# BuckConverter.net
KiCad netlist of a schematic drawn in Altium Designer
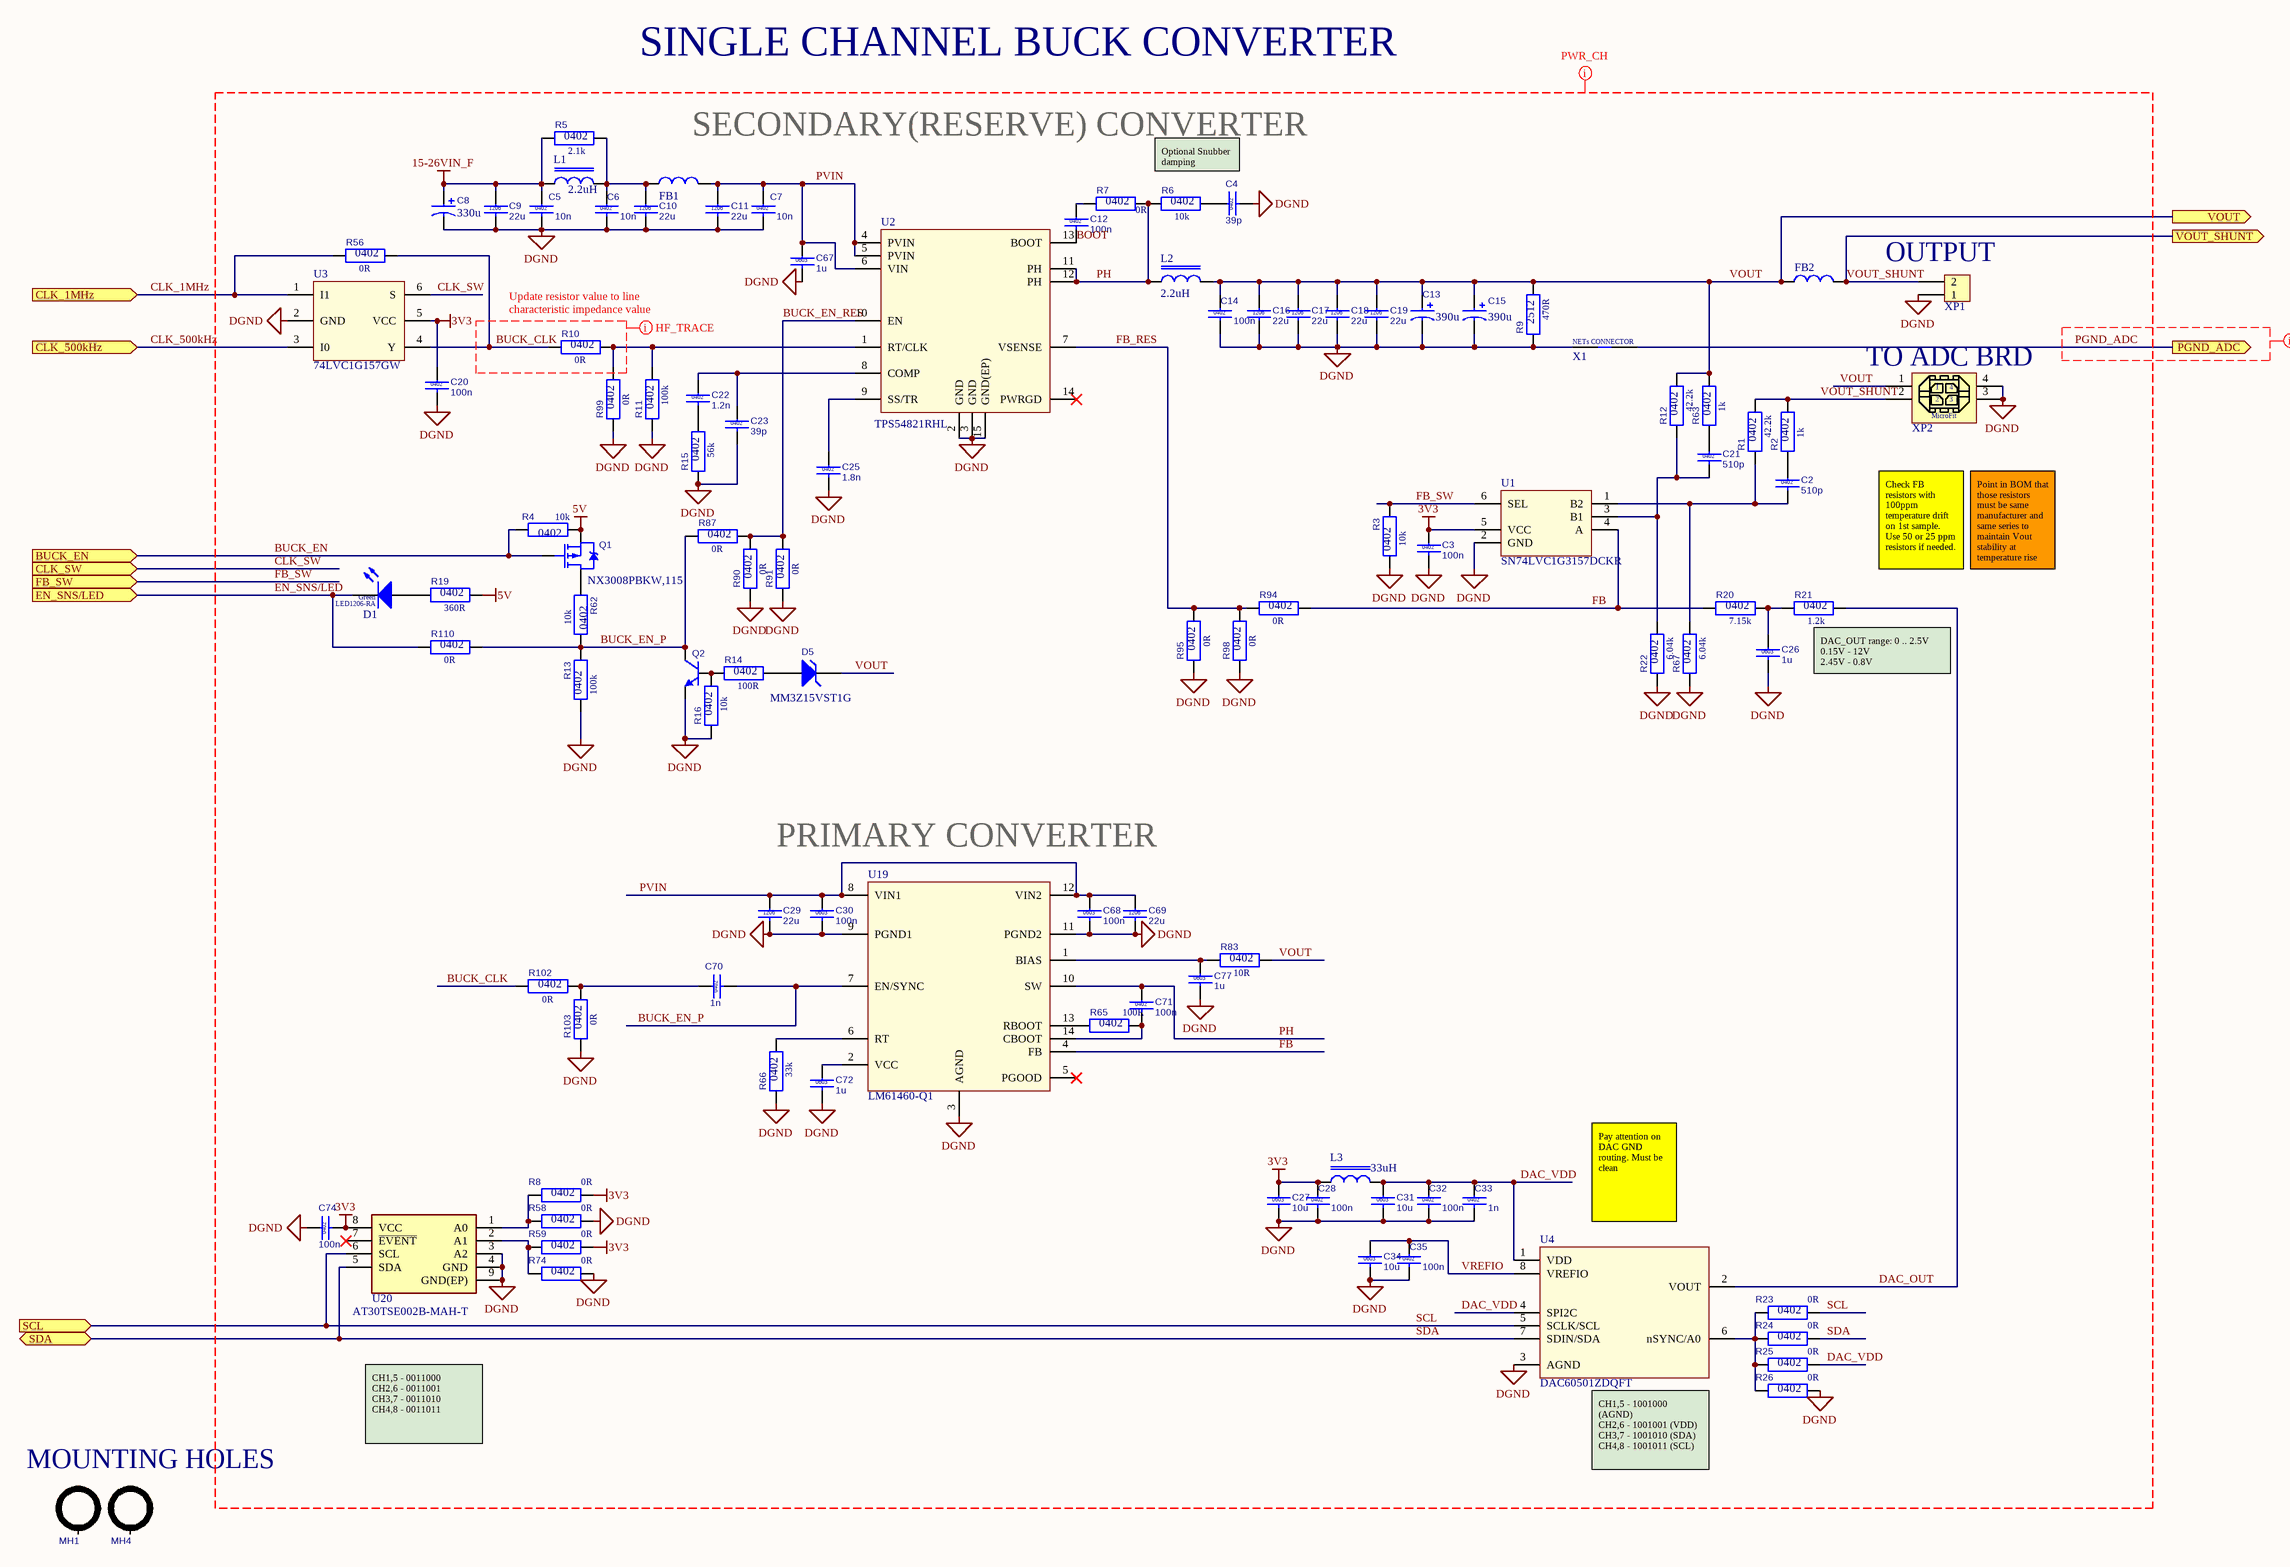
[diagram p0: BuckConverter.SchDoc]

(export (version "E")
  (design (tool "Eeschema 10.0.6"))
  (components
    (comp (ref "C2")
      (value "510p")
      (footprint "CC0402M")
      (description "Chip ceramic capacitor")
      (fields
        (field (name "CASE") "0402")
        (field (name "PARTNUMBER") "CC0402J-NP0-50V-510P-M")
        (field (name "MANUFACTURER") "Walsin")
      )
      (libsource (lib "AltiumLib") (part "Capacitor_nonpolar"))
    )
    (comp (ref "C3")
      (value "100n")
      (footprint "CC0402M")
      (description "Chip ceramic capacitor")
      (fields
        (field (name "CASE") "0402")
        (field (name "PARTNUMBER") "CC0402K-X7R-25V-100N-M")
        (field (name "MANUFACTURER") "Murata")
      )
      (libsource (lib "AltiumLib") (part "Capacitor_nonpolar"))
    )
    (comp (ref "C4")
      (value "39p")
      (footprint "CC0402M")
      (description "Chip ceramic capacitor")
      (fields
        (field (name "CASE") "0402")
        (field (name "PARTNUMBER") "CC0402J-NP0-50V-39P-M")
        (field (name "MANUFACTURER") "Yageo")
      )
      (libsource (lib "AltiumLib") (part "Capacitor_nonpolar"))
    )
    (comp (ref "C5")
      (value "10n")
      (footprint "CC0603M")
      (description "Chip ceramic capacitor")
      (fields
        (field (name "CASE") "0402")
        (field (name "PARTNUMBER") "CC0402K-X7R-50V-10N-M")
        (field (name "MANUFACTURER") "Yageo")
      )
      (libsource (lib "AltiumLib") (part "Capacitor_nonpolar"))
    )
    (comp (ref "C6")
      (value "10n")
      (footprint "CC0603M")
      (description "Chip ceramic capacitor")
      (fields
        (field (name "CASE") "0402")
        (field (name "PARTNUMBER") "CC0402K-X7R-50V-10N-M")
        (field (name "MANUFACTURER") "Yageo")
      )
      (libsource (lib "AltiumLib") (part "Capacitor_nonpolar"))
    )
    (comp (ref "C7")
      (value "10n")
      (footprint "CC0603M")
      (description "Chip ceramic capacitor")
      (fields
        (field (name "CASE") "0402")
        (field (name "PARTNUMBER") "CC0402K-X7R-50V-10N-M")
        (field (name "MANUFACTURER") "Yageo")
      )
      (libsource (lib "AltiumLib") (part "Capacitor_nonpolar"))
    )
    (comp (ref "C8")
      (value "330u")
      (footprint "CA-D10H10.5-SMD")
      (description "Aluminium Electrlytic capacitor")
      (fields (field (name "PARTNUMBER") "CE-L10D10-330U-35V-SMD") (field (name "MANUFACTURER") "Kemet"))
      (libsource (lib "AltiumLib") (part "Capacitor_polar"))
    )
    (comp (ref "C9")
      (value "22u")
      (footprint "CC1206M")
      (description "Chip ceramic capacitor")
      (fields
        (field (name "CASE") "1206")
        (field (name "PARTNUMBER") "CC1206K-X5R-35V-22U-M")
        (field (name "MANUFACTURER") "TDK")
      )
      (libsource (lib "AltiumLib") (part "Capacitor_nonpolar"))
    )
    (comp (ref "C10")
      (value "22u")
      (footprint "CC1206M")
      (description "Chip ceramic capacitor")
      (fields
        (field (name "CASE") "1206")
        (field (name "PARTNUMBER") "CC1206K-X5R-35V-22U-M")
        (field (name "MANUFACTURER") "TDK")
      )
      (libsource (lib "AltiumLib") (part "Capacitor_nonpolar"))
    )
    (comp (ref "C11")
      (value "22u")
      (footprint "CC1206M")
      (description "Chip ceramic capacitor")
      (fields
        (field (name "CASE") "1206")
        (field (name "PARTNUMBER") "CC1206K-X5R-35V-22U-M")
        (field (name "MANUFACTURER") "TDK")
      )
      (libsource (lib "AltiumLib") (part "Capacitor_nonpolar"))
    )
    (comp (ref "C12")
      (value "100n")
      (footprint "CC0402M")
      (description "Chip ceramic capacitor")
      (fields
        (field (name "CASE") "0402")
        (field (name "PARTNUMBER") "CC0402K-X7R-25V-100N-M")
        (field (name "MANUFACTURER") "Murata")
      )
      (libsource (lib "AltiumLib") (part "Capacitor_nonpolar"))
    )
    (comp (ref "C13")
      (value "390u")
      (footprint "CA-D8H12-SMD")
      (description "Aluminium polymer capacitor")
      (fields (field (name "PARTNUMBER") "20SVPF390M") (field (name "MANUFACTURER") "Panasonic"))
      (libsource (lib "AltiumLib") (part "Capacitor_polar"))
    )
    (comp (ref "C14")
      (value "100n")
      (footprint "CC0402M")
      (description "Chip ceramic capacitor")
      (fields
        (field (name "CASE") "0402")
        (field (name "PARTNUMBER") "CC0402K-X7R-25V-100N-M")
        (field (name "MANUFACTURER") "Murata")
      )
      (libsource (lib "AltiumLib") (part "Capacitor_nonpolar"))
    )
    (comp (ref "C15")
      (value "390u")
      (footprint "CA-D8H12-SMD")
      (description "Aluminium polymer capacitor")
      (fields (field (name "PARTNUMBER") "20SVPF390M") (field (name "MANUFACTURER") "Panasonic"))
      (libsource (lib "AltiumLib") (part "Capacitor_polar"))
    )
    (comp (ref "C16")
      (value "22u")
      (footprint "CC1206M")
      (description "Chip ceramic capacitor")
      (fields
        (field (name "CASE") "1206")
        (field (name "PARTNUMBER") "CC1206K-X5R-25V-22U-M")
        (field (name "MANUFACTURER") "Samsung")
      )
      (libsource (lib "AltiumLib") (part "Capacitor_nonpolar"))
    )
    (comp (ref "C17")
      (value "22u")
      (footprint "CC1206M")
      (description "Chip ceramic capacitor")
      (fields
        (field (name "CASE") "1206")
        (field (name "PARTNUMBER") "CC1206K-X5R-25V-22U-M")
        (field (name "MANUFACTURER") "Samsung")
      )
      (libsource (lib "AltiumLib") (part "Capacitor_nonpolar"))
    )
    (comp (ref "C18")
      (value "22u")
      (footprint "CC1206M")
      (description "Chip ceramic capacitor")
      (fields
        (field (name "CASE") "1206")
        (field (name "PARTNUMBER") "CC1206K-X5R-25V-22U-M")
        (field (name "MANUFACTURER") "Samsung")
      )
      (libsource (lib "AltiumLib") (part "Capacitor_nonpolar"))
    )
    (comp (ref "C19")
      (value "22u")
      (footprint "CC1206M")
      (description "Chip ceramic capacitor")
      (fields
        (field (name "CASE") "1206")
        (field (name "PARTNUMBER") "CC1206K-X5R-25V-22U-M")
        (field (name "MANUFACTURER") "Samsung")
      )
      (libsource (lib "AltiumLib") (part "Capacitor_nonpolar"))
    )
    (comp (ref "C20")
      (value "100n")
      (footprint "CC0402M")
      (description "Chip ceramic capacitor")
      (fields
        (field (name "CASE") "0402")
        (field (name "PARTNUMBER") "CC0402K-X7R-25V-100N-M")
        (field (name "MANUFACTURER") "Murata")
      )
      (libsource (lib "AltiumLib") (part "Capacitor_nonpolar"))
    )
    (comp (ref "C21")
      (value "510p")
      (footprint "CC0402M")
      (description "Chip ceramic capacitor")
      (fields
        (field (name "CASE") "0402")
        (field (name "PARTNUMBER") "CC0402J-NP0-50V-510P-M")
        (field (name "MANUFACTURER") "Walsin")
      )
      (libsource (lib "AltiumLib") (part "Capacitor_nonpolar"))
    )
    (comp (ref "C22")
      (value "1.2n")
      (footprint "CC0402M")
      (description "Chip ceramic capacitor")
      (fields
        (field (name "CASE") "0402")
        (field (name "PARTNUMBER") "CC0402K-X7R-50V-1N2-M")
        (field (name "MANUFACTURER") "Yageo")
      )
      (libsource (lib "AltiumLib") (part "Capacitor_nonpolar"))
    )
    (comp (ref "C23")
      (value "39p")
      (footprint "CC0402M")
      (description "Chip ceramic capacitor")
      (fields
        (field (name "CASE") "0402")
        (field (name "PARTNUMBER") "CC0402J-NP0-50V-39P-M")
        (field (name "MANUFACTURER") "Yageo")
      )
      (libsource (lib "AltiumLib") (part "Capacitor_nonpolar"))
    )
    (comp (ref "C25")
      (value "1.8n")
      (footprint "CC0402M")
      (description "Chip ceramic capacitor")
      (fields
        (field (name "CASE") "0402")
        (field (name "PARTNUMBER") "CC0402K-X7R-50V-1N8-M")
        (field (name "MANUFACTURER") "Yageo")
      )
      (libsource (lib "AltiumLib") (part "Capacitor_nonpolar"))
    )
    (comp (ref "C26")
      (value "1u")
      (footprint "CC0603M")
      (description "Chip ceramic capacitor")
      (fields
        (field (name "CASE") "0603")
        (field (name "PARTNUMBER") "CC0603K-X7R-10V-1U-M")
        (field (name "MANUFACTURER") "Samsung")
      )
      (libsource (lib "AltiumLib") (part "Capacitor_nonpolar"))
    )
    (comp (ref "C27")
      (value "10u")
      (footprint "CC0603M")
      (description "Chip ceramic capacitor")
      (fields
        (field (name "CASE") "0603")
        (field (name "PARTNUMBER") "CC0603K-X5R-10V-10U-M")
        (field (name "MANUFACTURER") "Murata")
      )
      (libsource (lib "AltiumLib") (part "Capacitor_nonpolar"))
    )
    (comp (ref "C28")
      (value "100n")
      (footprint "CC0402M")
      (description "Chip ceramic capacitor")
      (fields
        (field (name "CASE") "0402")
        (field (name "PARTNUMBER") "CC0402K-X7R-25V-100N-M")
        (field (name "MANUFACTURER") "Murata")
      )
      (libsource (lib "AltiumLib") (part "Capacitor_nonpolar"))
    )
    (comp (ref "C29")
      (value "22u")
      (footprint "CC1206M")
      (description "Chip ceramic capacitor")
      (fields
        (field (name "CASE") "1206")
        (field (name "PARTNUMBER") "CC1206K-X5R-35V-22U-M")
        (field (name "MANUFACTURER") "TDK")
      )
      (libsource (lib "AltiumLib") (part "Capacitor_nonpolar"))
    )
    (comp (ref "C30")
      (value "100n")
      (footprint "CC0603M")
      (description "Chip ceramic capacitor")
      (fields
        (field (name "CASE") "0603")
        (field (name "PARTNUMBER") "CC0603K-X7R-50V-100N-M")
        (field (name "MANUFACTURER") "Yageo")
      )
      (libsource (lib "AltiumLib") (part "Capacitor_nonpolar"))
    )
    (comp (ref "C31")
      (value "10u")
      (footprint "CC0603M")
      (description "Chip ceramic capacitor")
      (fields
        (field (name "CASE") "0603")
        (field (name "PARTNUMBER") "CC0603K-X5R-10V-10U-M")
        (field (name "MANUFACTURER") "Murata")
      )
      (libsource (lib "AltiumLib") (part "Capacitor_nonpolar"))
    )
    (comp (ref "C32")
      (value "100n")
      (footprint "CC0402M")
      (description "Chip ceramic capacitor")
      (fields
        (field (name "CASE") "0402")
        (field (name "PARTNUMBER") "CC0402K-X7R-25V-100N-M")
        (field (name "MANUFACTURER") "Murata")
      )
      (libsource (lib "AltiumLib") (part "Capacitor_nonpolar"))
    )
    (comp (ref "C33")
      (value "1n")
      (footprint "CC0402M")
      (description "Chip ceramic capacitor")
      (fields
        (field (name "CASE") "0402")
        (field (name "PARTNUMBER") "CC0402K-X7R-50V-1N-M")
        (field (name "MANUFACTURER") "Yageo")
      )
      (libsource (lib "AltiumLib") (part "Capacitor_nonpolar"))
    )
    (comp (ref "C34")
      (value "10u")
      (footprint "CC0603M")
      (description "Chip ceramic capacitor")
      (fields
        (field (name "CASE") "0603")
        (field (name "PARTNUMBER") "CC0603K-X5R-10V-10U-M")
        (field (name "MANUFACTURER") "Murata")
      )
      (libsource (lib "AltiumLib") (part "Capacitor_nonpolar"))
    )
    (comp (ref "C35")
      (value "100n")
      (footprint "CC0402M")
      (description "Chip ceramic capacitor")
      (fields
        (field (name "CASE") "0402")
        (field (name "PARTNUMBER") "CC0402K-X7R-25V-100N-M")
        (field (name "MANUFACTURER") "Murata")
      )
      (libsource (lib "AltiumLib") (part "Capacitor_nonpolar"))
    )
    (comp (ref "C67")
      (value "1u")
      (footprint "CC0603M")
      (description "Chip ceramic capacitor")
      (fields
        (field (name "CASE") "0603")
        (field (name "PARTNUMBER") "CC0603K-X5R-50V-1U-M")
        (field (name "MANUFACTURER") "Samsung")
      )
      (libsource (lib "AltiumLib") (part "Capacitor_nonpolar"))
    )
    (comp (ref "C68")
      (value "100n")
      (footprint "CC0603M")
      (description "Chip ceramic capacitor")
      (fields
        (field (name "CASE") "0603")
        (field (name "PARTNUMBER") "CC0603K-X7R-50V-100N-M")
        (field (name "MANUFACTURER") "Yageo")
      )
      (libsource (lib "AltiumLib") (part "Capacitor_nonpolar"))
    )
    (comp (ref "C69")
      (value "22u")
      (footprint "CC1206M")
      (description "Chip ceramic capacitor")
      (fields
        (field (name "CASE") "1206")
        (field (name "PARTNUMBER") "CC1206K-X5R-35V-22U-M")
        (field (name "MANUFACTURER") "TDK")
      )
      (libsource (lib "AltiumLib") (part "Capacitor_nonpolar"))
    )
    (comp (ref "C70")
      (value "1n")
      (footprint "CC0402M")
      (description "Chip ceramic capacitor")
      (fields
        (field (name "CASE") "0402")
        (field (name "PARTNUMBER") "CC0402K-X7R-50V-1N-M")
        (field (name "MANUFACTURER") "Yageo")
      )
      (libsource (lib "AltiumLib") (part "Capacitor_nonpolar"))
    )
    (comp (ref "C71")
      (value "100n")
      (footprint "CC0402M")
      (description "Chip ceramic capacitor")
      (fields
        (field (name "CASE") "0402")
        (field (name "PARTNUMBER") "CC0402K-X7R-25V-100N-M")
        (field (name "MANUFACTURER") "Murata")
      )
      (libsource (lib "AltiumLib") (part "Capacitor_nonpolar"))
    )
    (comp (ref "C72")
      (value "1u")
      (footprint "CC0603M")
      (description "Chip ceramic capacitor")
      (fields
        (field (name "CASE") "0603")
        (field (name "PARTNUMBER") "CC0603K-X5R-50V-1U-M")
        (field (name "MANUFACTURER") "Samsung")
      )
      (libsource (lib "AltiumLib") (part "Capacitor_nonpolar"))
    )
    (comp (ref "C74")
      (value "100n")
      (footprint "CC0402M")
      (description "Chip ceramic capacitor")
      (fields
        (field (name "CASE") "0402")
        (field (name "PARTNUMBER") "CC0402K-X7R-25V-100N-M")
        (field (name "MANUFACTURER") "Murata")
      )
      (libsource (lib "AltiumLib") (part "Capacitor_nonpolar"))
    )
    (comp (ref "C77")
      (value "1u")
      (footprint "CC0603M")
      (description "Chip ceramic capacitor")
      (fields
        (field (name "CASE") "0603")
        (field (name "PARTNUMBER") "CC0603K-X5R-50V-1U-M")
        (field (name "MANUFACTURER") "Samsung")
      )
      (libsource (lib "AltiumLib") (part "Capacitor_nonpolar"))
    )
    (comp (ref "D1")
      (value "155124GS73200A")
      (footprint "LED1206-RA")
      (description "LED GREEN CLEAR 1206 SMD RA")
      (fields
        (field (name "CASE") "LED1206-RA")
        (field (name "COLOR") "Green")
        (field (name "MANUFACTURER") "Würth Elektronik")
      )
      (libsource (lib "AltiumLib") (part "LED"))
    )
    (comp (ref "D5")
      (value "MM3Z15VST1G")
      (footprint "SOD323")
      (description "Zener Diode 14.66V 300mW ±2% Surface Mount SOD-323")
      (fields (field (name "MANUFACTURER") "ON Semiconductor"))
      (libsource (lib "AltiumLib") (part "ZENNER_DIODE"))
    )
    (comp (ref "FB1")
      (value "BLM21SP601SH1D")
      (footprint "FB0805M")
      (description "600 Ohms @ 100MHz 1 Power Line Ferrite Bead 0805 (2012 Metric) 2.3A")
      (fields (field (name "MANUFACTURER") "Murata"))
      (libsource (lib "AltiumLib") (part "FerriteBead"))
    )
    (comp (ref "FB2")
      (value "BLM18KG260TN1D")
      (footprint "FB0603M")
      (description "26 Ohms @ 100MHz 1 Power Line Ferrite Bead 0603 (1608 Metric) 6A 7mOhm")
      (fields (field (name "MANUFACTURER") "Murata"))
      (libsource (lib "AltiumLib") (part "FerriteBead"))
    )
    (comp (ref "L1")
      (value "2.2uH")
      (footprint "MGV252010S")
      (description "2.2µH Shielded Molded Inductor 2.4A 110mOhm Max 1008 (2520 Metric)")
      (fields
        (field (name "PARTNUMBER") "MGV252010S2R2M-10")
        (field (name "MANUFACTURER") "Laird-Signal Integrity Products")
      )
      (libsource (lib "AltiumLib") (part "Inductor"))
    )
    (comp (ref "L2")
      (value "2.2uH")
      (footprint "104CDMCCDS")
      (description "FIXED IND 2.2UH 15A 7 MOHM")
      (fields (field (name "PARTNUMBER") "104CDMCCDS-2R2MC") (field (name "MANUFACTURER") "Sumida"))
      (libsource (lib "AltiumLib") (part "Inductor"))
    )
    (comp (ref "L3")
      (value "33uH")
      (footprint "IC0805-M")
      (description "FIXED IND 33UH 5MA 1.25 OHM SMD")
      (fields (field (name "PARTNUMBER") "CV201210-330K") (field (name "MANUFACTURER") "Bourns"))
      (libsource (lib "AltiumLib") (part "Inductor"))
    )
    (comp (ref "MH1")
      (value "MH-3.5-PLATED")
      (footprint "MH_3.5_PLATED")
      (description "Mounting Hole")
      (fields (field (name "MANUFACTURER") "NULL"))
      (libsource (lib "AltiumLib") (part "MH_MISC"))
    )
    (comp (ref "MH4")
      (value "MH-3.5-PLATED")
      (footprint "MH_3.5_PLATED")
      (description "Mounting Hole")
      (fields (field (name "MANUFACTURER") "NULL"))
      (libsource (lib "AltiumLib") (part "MH_MISC"))
    )
    (comp (ref "Q1")
      (value "NX3008PBKW,115")
      (footprint "SOT323")
      (description "P-Channel 30V 200mA (Ta) 260mW (Ta), 830mW (Tc) Surface Mount SC-70")
      (fields (field (name "MANUFACTURER") "Nexperia"))
      (libsource (lib "AltiumLib") (part "MOSFET_P-CH"))
    )
    (comp (ref "Q2")
      (value "NPN_transistor_SOT23-3")
      (footprint "SOT323")
      (description "TRANS NPN 40V 0.2A SOT323")
      (fields (field (name "PARTNUMBER") "MMBT3904WT1G") (field (name "MANUFACTURER") "ON Semiconductor"))
      (libsource (lib "AltiumLib") (part "NPN_SOT23-3"))
    )
    (comp (ref "R1")
      (value "42.2k")
      (footprint "RC0402M")
      (description "Chip resistor")
      (fields
        (field (name "CASE") "0402")
        (field (name "PARTNUMBER") "RC0402F-42K2-M")
        (field (name "POWER") "0.063W")
      )
      (libsource (lib "AltiumLib") (part "Resistor"))
    )
    (comp (ref "R2")
      (value "1k")
      (footprint "RC0402M")
      (description "Chip resistor")
      (fields
        (field (name "CASE") "0402")
        (field (name "PARTNUMBER") "RC0402F-1K-M")
        (field (name "MANUFACTURER") "Yageo")
      )
      (libsource (lib "AltiumLib") (part "Resistor"))
    )
    (comp (ref "R3")
      (value "10k")
      (footprint "RC0402M")
      (description "Chip resistor")
      (fields
        (field (name "CASE") "0402")
        (field (name "PARTNUMBER") "RC0402F-10K-M")
        (field (name "MANUFACTURER") "Yageo")
      )
      (libsource (lib "AltiumLib") (part "Resistor"))
    )
    (comp (ref "R4")
      (value "10k")
      (footprint "RC0402M")
      (description "Chip resistor")
      (fields
        (field (name "CASE") "0402")
        (field (name "PARTNUMBER") "RC0402F-10K-M")
        (field (name "MANUFACTURER") "Yageo")
      )
      (libsource (lib "AltiumLib") (part "Resistor"))
    )
    (comp (ref "R5")
      (value "2.1k")
      (footprint "RC0402M")
      (description "Chip resistor")
      (fields
        (field (name "CASE") "0402")
        (field (name "PARTNUMBER") "RC0402F-2K1-M")
        (field (name "POWER") "0.063W")
      )
      (libsource (lib "AltiumLib") (part "Resistor"))
    )
    (comp (ref "R6")
      (value "10k")
      (footprint "RC0402M")
      (description "Chip resistor")
      (fields
        (field (name "CASE") "0402")
        (field (name "PARTNUMBER") "RC0402F-10K-M")
        (field (name "POWER") "0.063W")
      )
      (libsource (lib "AltiumLib") (part "Resistor"))
    )
    (comp (ref "R7")
      (value "0R")
      (footprint "RC0402M")
      (description "Chip resistor")
      (fields
        (field (name "CASE") "0402")
        (field (name "PARTNUMBER") "RC0402F-0R-M")
        (field (name "POWER") "0.063W")
      )
      (libsource (lib "AltiumLib") (part "Resistor"))
    )
    (comp (ref "R8")
      (value "0R")
      (footprint "RC0402M")
      (description "Chip resistor")
      (fields
        (field (name "CASE") "0402")
        (field (name "PARTNUMBER") "RC0402F-0R-M")
        (field (name "POWER") "0.063W")
      )
      (libsource (lib "AltiumLib") (part "Resistor"))
    )
    (comp (ref "R9")
      (value "470R")
      (footprint "RC2512M")
      (description "Chip resistor")
      (fields
        (field (name "CASE") "2512")
        (field (name "PARTNUMBER") "RC2512J-479R-M")
        (field (name "MANUFACTURER") "Stackpole")
      )
      (libsource (lib "AltiumLib") (part "Resistor"))
    )
    (comp (ref "R10")
      (value "0R")
      (footprint "RC0402M")
      (description "Chip resistor")
      (fields
        (field (name "CASE") "0402")
        (field (name "PARTNUMBER") "RC0402F-0R-M")
        (field (name "POWER") "0.063W")
      )
      (libsource (lib "AltiumLib") (part "Resistor"))
    )
    (comp (ref "R11")
      (value "100k")
      (footprint "RC0402M")
      (description "Chip resistor")
      (fields
        (field (name "CASE") "0402")
        (field (name "PARTNUMBER") "RC0402F-100K-M")
        (field (name "POWER") "0.063W")
      )
      (libsource (lib "AltiumLib") (part "Resistor"))
    )
    (comp (ref "R12")
      (value "42.2k")
      (footprint "RC0402M")
      (description "Chip resistor")
      (fields
        (field (name "CASE") "0402")
        (field (name "PARTNUMBER") "RC0402F-42K2-M")
        (field (name "POWER") "0.063W")
      )
      (libsource (lib "AltiumLib") (part "Resistor"))
    )
    (comp (ref "R13")
      (value "100k")
      (footprint "RC0402M")
      (description "Chip resistor")
      (fields
        (field (name "CASE") "0402")
        (field (name "PARTNUMBER") "RC0402F-100K-M")
        (field (name "MANUFACTURER") "Yageo")
      )
      (libsource (lib "AltiumLib") (part "Resistor"))
    )
    (comp (ref "R14")
      (value "100R")
      (footprint "RC0402M")
      (description "Chip resistor")
      (fields
        (field (name "CASE") "0402")
        (field (name "PARTNUMBER") "RC0402F-100R-M")
        (field (name "MANUFACTURER") "Yageo")
      )
      (libsource (lib "AltiumLib") (part "Resistor"))
    )
    (comp (ref "R15")
      (value "56k")
      (footprint "RC0402M")
      (description "Chip resistor")
      (fields
        (field (name "CASE") "0402")
        (field (name "PARTNUMBER") "RC0402F-56K-M")
        (field (name "POWER") "0.063W")
      )
      (libsource (lib "AltiumLib") (part "Resistor"))
    )
    (comp (ref "R16")
      (value "10k")
      (footprint "RC0402M")
      (description "Chip resistor")
      (fields
        (field (name "CASE") "0402")
        (field (name "PARTNUMBER") "RC0402F-10K-M")
        (field (name "MANUFACTURER") "Yageo")
      )
      (libsource (lib "AltiumLib") (part "Resistor"))
    )
    (comp (ref "R19")
      (value "360R")
      (footprint "RC0402M")
      (description "Chip resistor")
      (fields
        (field (name "CASE") "0402")
        (field (name "PARTNUMBER") "RC0402F-360R-M")
        (field (name "MANUFACTURER") "Yageo")
      )
      (libsource (lib "AltiumLib") (part "Resistor"))
    )
    (comp (ref "R20")
      (value "7.15k")
      (footprint "RC0402M")
      (description "Chip resistor")
      (fields
        (field (name "CASE") "0402")
        (field (name "PARTNUMBER") "RC0402F-7K15-M")
        (field (name "MANUFACTURER") "Yageo")
      )
      (libsource (lib "AltiumLib") (part "Resistor"))
    )
    (comp (ref "R21")
      (value "1.2k")
      (footprint "RC0402M")
      (description "Chip resistor")
      (fields
        (field (name "CASE") "0402")
        (field (name "PARTNUMBER") "RC0402F-1K2-M")
        (field (name "MANUFACTURER") "Yageo")
      )
      (libsource (lib "AltiumLib") (part "Resistor"))
    )
    (comp (ref "R22")
      (value "6.04k")
      (footprint "RC0402M")
      (description "Chip resistor")
      (fields
        (field (name "CASE") "0402")
        (field (name "PARTNUMBER") "RC0402F-6K04-M")
        (field (name "MANUFACTURER") "Yageo")
      )
      (libsource (lib "AltiumLib") (part "Resistor"))
    )
    (comp (ref "R23")
      (value "0R")
      (footprint "RC0402M")
      (description "Chip resistor")
      (fields
        (field (name "CASE") "0402")
        (field (name "PARTNUMBER") "RC0402F-0R-M")
        (field (name "POWER") "0.063W")
      )
      (libsource (lib "AltiumLib") (part "Resistor"))
    )
    (comp (ref "R24")
      (value "0R")
      (footprint "RC0402M")
      (description "Chip resistor")
      (fields
        (field (name "CASE") "0402")
        (field (name "PARTNUMBER") "RC0402F-0R-M")
        (field (name "POWER") "0.063W")
      )
      (libsource (lib "AltiumLib") (part "Resistor"))
    )
    (comp (ref "R25")
      (value "0R")
      (footprint "RC0402M")
      (description "Chip resistor")
      (fields
        (field (name "CASE") "0402")
        (field (name "PARTNUMBER") "RC0402F-0R-M")
        (field (name "POWER") "0.063W")
      )
      (libsource (lib "AltiumLib") (part "Resistor"))
    )
    (comp (ref "R26")
      (value "0R")
      (footprint "RC0402M")
      (description "Chip resistor")
      (fields
        (field (name "CASE") "0402")
        (field (name "PARTNUMBER") "RC0402F-0R-M")
        (field (name "POWER") "0.063W")
      )
      (libsource (lib "AltiumLib") (part "Resistor"))
    )
    (comp (ref "R56")
      (value "0R")
      (footprint "RC0402M")
      (description "Chip resistor")
      (fields
        (field (name "CASE") "0402")
        (field (name "PARTNUMBER") "RC0402F-0R-M")
        (field (name "POWER") "0.063W")
      )
      (libsource (lib "AltiumLib") (part "Resistor"))
    )
    (comp (ref "R58")
      (value "0R")
      (footprint "RC0402M")
      (description "Chip resistor")
      (fields
        (field (name "CASE") "0402")
        (field (name "PARTNUMBER") "RC0402F-0R-M")
        (field (name "POWER") "0.063W")
      )
      (libsource (lib "AltiumLib") (part "Resistor"))
    )
    (comp (ref "R59")
      (value "0R")
      (footprint "RC0402M")
      (description "Chip resistor")
      (fields
        (field (name "CASE") "0402")
        (field (name "PARTNUMBER") "RC0402F-0R-M")
        (field (name "POWER") "0.063W")
      )
      (libsource (lib "AltiumLib") (part "Resistor"))
    )
    (comp (ref "R62")
      (value "10k")
      (footprint "RC0402M")
      (description "Chip resistor")
      (fields
        (field (name "CASE") "0402")
        (field (name "PARTNUMBER") "RC0402F-10K-M")
        (field (name "MANUFACTURER") "Yageo")
      )
      (libsource (lib "AltiumLib") (part "Resistor"))
    )
    (comp (ref "R63")
      (value "1k")
      (footprint "RC0402M")
      (description "Chip resistor")
      (fields
        (field (name "CASE") "0402")
        (field (name "PARTNUMBER") "RC0402F-1K-M")
        (field (name "MANUFACTURER") "Yageo")
      )
      (libsource (lib "AltiumLib") (part "Resistor"))
    )
    (comp (ref "R65")
      (value "100R")
      (footprint "RC0402M")
      (description "Chip resistor")
      (fields
        (field (name "CASE") "0402")
        (field (name "PARTNUMBER") "RC0402F-100R-M")
        (field (name "MANUFACTURER") "Yageo")
      )
      (libsource (lib "AltiumLib") (part "Resistor"))
    )
    (comp (ref "R66")
      (value "33k")
      (footprint "RC0402M")
      (description "Chip resistor")
      (fields
        (field (name "CASE") "0402")
        (field (name "PARTNUMBER") "RC0402F-33K-M")
        (field (name "MANUFACTURER") "Yageo")
      )
      (libsource (lib "AltiumLib") (part "Resistor"))
    )
    (comp (ref "R67")
      (value "6.04k")
      (footprint "RC0402M")
      (description "Chip resistor")
      (fields
        (field (name "CASE") "0402")
        (field (name "PARTNUMBER") "RC0402F-6K04-M")
        (field (name "MANUFACTURER") "Yageo")
      )
      (libsource (lib "AltiumLib") (part "Resistor"))
    )
    (comp (ref "R74")
      (value "0R")
      (footprint "RC0402M")
      (description "Chip resistor")
      (fields
        (field (name "CASE") "0402")
        (field (name "PARTNUMBER") "RC0402F-0R-M")
        (field (name "POWER") "0.063W")
      )
      (libsource (lib "AltiumLib") (part "Resistor"))
    )
    (comp (ref "R83")
      (value "10R")
      (footprint "RC0402M")
      (description "Chip resistor")
      (fields
        (field (name "CASE") "0402")
        (field (name "PARTNUMBER") "RC0402F-10R-M")
        (field (name "MANUFACTURER") "Yageo")
      )
      (libsource (lib "AltiumLib") (part "Resistor"))
    )
    (comp (ref "R87")
      (value "0R")
      (footprint "RC0402M")
      (description "Chip resistor")
      (fields
        (field (name "CASE") "0402")
        (field (name "PARTNUMBER") "RC0402F-0R-M")
        (field (name "MANUFACTURER") "Yageo")
      )
      (libsource (lib "AltiumLib") (part "Resistor"))
    )
    (comp (ref "R90")
      (value "0R")
      (footprint "RC0402M")
      (description "Chip resistor")
      (fields
        (field (name "CASE") "0402")
        (field (name "PARTNUMBER") "RC0402F-0R-M")
        (field (name "MANUFACTURER") "Yageo")
      )
      (libsource (lib "AltiumLib") (part "Resistor"))
    )
    (comp (ref "R91")
      (value "0R")
      (footprint "RC0402M")
      (description "Chip resistor")
      (fields
        (field (name "CASE") "0402")
        (field (name "PARTNUMBER") "RC0402F-0R-M")
        (field (name "MANUFACTURER") "Yageo")
      )
      (libsource (lib "AltiumLib") (part "Resistor"))
    )
    (comp (ref "R94")
      (value "0R")
      (footprint "RC0402M")
      (description "Chip resistor")
      (fields
        (field (name "CASE") "0402")
        (field (name "PARTNUMBER") "RC0402F-0R-M")
        (field (name "MANUFACTURER") "Yageo")
      )
      (libsource (lib "AltiumLib") (part "Resistor"))
    )
    (comp (ref "R95")
      (value "0R")
      (footprint "RC0402M")
      (description "Chip resistor")
      (fields
        (field (name "CASE") "0402")
        (field (name "PARTNUMBER") "RC0402F-0R-M")
        (field (name "MANUFACTURER") "Yageo")
      )
      (libsource (lib "AltiumLib") (part "Resistor"))
    )
    (comp (ref "R98")
      (value "0R")
      (footprint "RC0402M")
      (description "Chip resistor")
      (fields
        (field (name "CASE") "0402")
        (field (name "PARTNUMBER") "RC0402F-0R-M")
        (field (name "MANUFACTURER") "Yageo")
      )
      (libsource (lib "AltiumLib") (part "Resistor"))
    )
    (comp (ref "R99")
      (value "0R")
      (footprint "RC0402M")
      (description "Chip resistor")
      (fields
        (field (name "CASE") "0402")
        (field (name "PARTNUMBER") "RC0402F-0R-M")
        (field (name "POWER") "0.063W")
      )
      (libsource (lib "AltiumLib") (part "Resistor"))
    )
    (comp (ref "R102")
      (value "0R")
      (footprint "RC0402M")
      (description "Chip resistor")
      (fields
        (field (name "CASE") "0402")
        (field (name "PARTNUMBER") "RC0402F-0R-M")
        (field (name "POWER") "0.063W")
      )
      (libsource (lib "AltiumLib") (part "Resistor"))
    )
    (comp (ref "R103")
      (value "0R")
      (footprint "RC0402M")
      (description "Chip resistor")
      (fields
        (field (name "CASE") "0402")
        (field (name "PARTNUMBER") "RC0402F-0R-M")
        (field (name "POWER") "0.063W")
      )
      (libsource (lib "AltiumLib") (part "Resistor"))
    )
    (comp (ref "R110")
      (value "0R")
      (footprint "RC0402M")
      (description "Chip resistor")
      (fields
        (field (name "CASE") "0402")
        (field (name "PARTNUMBER") "RC0402F-0R-M")
        (field (name "MANUFACTURER") "Yageo")
      )
      (libsource (lib "AltiumLib") (part "Resistor"))
    )
    (comp (ref "U1")
      (value "SN74LVC1G3157DCKR")
      (footprint "SOT363")
      (description "1 Circuit IC Switch 2:1 10Ohm SOT-363")
      (fields (field (name "MANUFACTURER") "TI"))
      (libsource (lib "AltiumLib") (part "1G3157"))
    )
    (comp (ref "U2")
      (value "TPS54821RHL")
      (footprint "VQFN-14")
      (description "IC REG BUCK ADJUSTABLE 8A 14VQFN")
      (fields (field (name "MANUFACTURER") "TI"))
      (libsource (lib "AltiumLib") (part "TPS54821RHL"))
    )
    (comp (ref "U3")
      (value "74LVC1G157GW")
      (footprint "SOT363")
      (description "IC SINGLE 2-INPUT MUX 6TSSOP")
      (fields (field (name "MANUFACTURER") "Nexperia"))
      (libsource (lib "AltiumLib") (part "74LVC1G157"))
    )
    (comp (ref "U4")
      (value "DAC60501ZDQFT")
      (footprint "WSON-8")
      (description "SINGLE CHAN DAC 24BIT- ZEROCODE")
      (fields (field (name "MANUFACTURER") "TI"))
      (libsource (lib "AltiumLib") (part "DACx0501"))
    )
    (comp (ref "U19")
      (value "LM61460-Q1")
      (footprint "VQFN-HR-14")
      (description "Buck Switching Regulator IC Positive Adjustable 1V 1 Output 6A 14-VFQFN")
      (fields (field (name "MANUFACTURER") "TI"))
      (libsource (lib "AltiumLib") (part "LM61460-Q1"))
    )
    (comp (ref "U20")
      (value "AT30TSE002B-MAH-T")
      (footprint "WDFN-8")
      (description "Temperature Sensor Digital, Local -20°C ~ 125°C 10 b 8-WDFN (2x3)")
      (fields (field (name "MANUFACTURER") "Microchip"))
      (libsource (lib "AltiumLib") (part "AT30TSE002B"))
    )
    (comp (ref "X1")
      (value "NETs_CONNECTOR")
      (footprint "NETs_CONNECTOR")
      (description "No BOM component to short circuit 2 nets")
      (fields (field (name "MANUFACTURER") "NULL"))
      (libsource (lib "AltiumLib") (part "NETs_CONNECTOR"))
    )
    (comp (ref "XP1")
      (value "TBH-2x3.81P-RA-GN")
      (footprint "TBH-2x3.81P-RA-GN")
      (fields (field (name "MANUFACTURER") "Würth Elektronik"))
      (libsource (lib "AltiumLib") (part "TBH-2x"))
    )
    (comp (ref "XP2")
      (value "0447690401")
      (footprint "0447690401")
      (fields (field (name "MANUFACTURER") "Molex"))
      (libsource (lib "AltiumLib") (part "MicroFit-2x2"))
    )
  )
  (nets
    (net (code "1") (name "/BOOT") (class "Default")
      (node (ref "C12") (pin "2") (pinfunction "2_2") (pintype "passive"))
      (node (ref "U2") (pin "13") (pinfunction "BOOT_13") (pintype "passive"))
    )
    (net (code "2") (name "/BUCK_CLK") (class "Default")
      (node (ref "R10") (pin "1") (pinfunction "1_1") (pintype "passive"))
      (node (ref "R102") (pin "1") (pinfunction "1_1") (pintype "passive"))
      (node (ref "R56") (pin "2") (pinfunction "2_2") (pintype "passive"))
      (node (ref "U3") (pin "4") (pinfunction "Y_4") (pintype "passive"))
    )
    (net (code "3") (name "/BUCK_EN") (class "Default")
      (node (ref "Q1") (pin "1") (pinfunction "G_1") (pintype "passive"))
      (node (ref "R4") (pin "1") (pinfunction "1_1") (pintype "passive"))
    )
    (net (code "4") (name "/BUCK_EN_P") (class "Default")
      (node (ref "C70") (pin "2") (pinfunction "2_2") (pintype "passive"))
      (node (ref "Q2") (pin "3") (pinfunction "C_3") (pintype "passive"))
      (node (ref "R110") (pin "2") (pinfunction "2_2") (pintype "passive"))
      (node (ref "R13") (pin "1") (pinfunction "1_1") (pintype "passive"))
      (node (ref "R62") (pin "2") (pinfunction "2_2") (pintype "passive"))
      (node (ref "R87") (pin "1") (pinfunction "1_1") (pintype "passive"))
      (node (ref "U19") (pin "7") (pinfunction "EN/SYNC_7") (pintype "passive"))
    )
    (net (code "5") (name "/BUCK_EN_RES") (class "Default")
      (node (ref "R87") (pin "2") (pinfunction "2_2") (pintype "passive"))
      (node (ref "R90") (pin "2") (pinfunction "2_2") (pintype "passive"))
      (node (ref "R91") (pin "2") (pinfunction "2_2") (pintype "passive"))
      (node (ref "U2") (pin "10") (pinfunction "EN_10") (pintype "passive"))
    )
    (net (code "6") (name "/CLK_1MHz") (class "Default")
      (node (ref "R56") (pin "1") (pinfunction "1_1") (pintype "passive"))
      (node (ref "U3") (pin "1") (pinfunction "I1_1") (pintype "passive"))
    )
    (net (code "7") (name "/CLK_500kHz") (class "Default")
      (node (ref "U3") (pin "3") (pinfunction "I0_3") (pintype "passive"))
    )
    (net (code "8") (name "/CLK_SW") (class "Default")
      (node (ref "U3") (pin "6") (pinfunction "S_6") (pintype "passive"))
    )
    (net (code "9") (name "/DAC_OUT") (class "Default")
      (node (ref "R21") (pin "2") (pinfunction "2_2") (pintype "passive"))
      (node (ref "U4") (pin "2") (pinfunction "VOUT_2") (pintype "passive"))
    )
    (net (code "10") (name "/DAC_VDD") (class "Default")
      (node (ref "C31") (pin "1") (pinfunction "1_1") (pintype "passive"))
      (node (ref "C32") (pin "1") (pinfunction "1_1") (pintype "passive"))
      (node (ref "C33") (pin "1") (pinfunction "1_1") (pintype "passive"))
      (node (ref "L3") (pin "2") (pinfunction "2_2") (pintype "passive"))
      (node (ref "R25") (pin "2") (pinfunction "2_2") (pintype "passive"))
      (node (ref "U4") (pin "1") (pinfunction "VDD_1") (pintype "passive"))
      (node (ref "U4") (pin "4") (pinfunction "SPI2C_4") (pintype "passive"))
    )
    (net (code "11") (name "/EN_SNS{slash}LED") (class "Default")
      (node (ref "D1") (pin "1") (pinfunction "K_1") (pintype "passive"))
      (node (ref "R110") (pin "1") (pinfunction "1_1") (pintype "passive"))
    )
    (net (code "12") (name "/FB") (class "Default")
      (node (ref "R20") (pin "1") (pinfunction "1_1") (pintype "passive"))
      (node (ref "R94") (pin "2") (pinfunction "2_2") (pintype "passive"))
      (node (ref "U1") (pin "4") (pinfunction "A_4") (pintype "passive"))
      (node (ref "U19") (pin "4") (pinfunction "FB_4") (pintype "passive"))
    )
    (net (code "13") (name "/FB_RES") (class "Default")
      (node (ref "R94") (pin "1") (pinfunction "1_1") (pintype "passive"))
      (node (ref "R95") (pin "2") (pinfunction "2_2") (pintype "passive"))
      (node (ref "R98") (pin "2") (pinfunction "2_2") (pintype "passive"))
      (node (ref "U2") (pin "7") (pinfunction "VSENSE_7") (pintype "passive"))
    )
    (net (code "14") (name "/FB_SW") (class "Default")
      (node (ref "R3") (pin "1") (pinfunction "1_1") (pintype "passive"))
      (node (ref "U1") (pin "6") (pinfunction "SEL_6") (pintype "passive"))
    )
    (net (code "15") (name "/PGND_ADC") (class "Default")
      (node (ref "X1") (pin "2") (pinfunction "2_2") (pintype "passive"))
    )
    (net (code "16") (name "/PH") (class "Default")
      (node (ref "C71") (pin "1") (pinfunction "1_1") (pintype "passive"))
      (node (ref "L2") (pin "1") (pinfunction "1_1") (pintype "passive"))
      (node (ref "R6") (pin "1") (pinfunction "1_1") (pintype "passive"))
      (node (ref "R7") (pin "2") (pinfunction "2_2") (pintype "passive"))
      (node (ref "U19") (pin "10") (pinfunction "SW_10") (pintype "passive"))
      (node (ref "U2") (pin "11") (pinfunction "PH_11") (pintype "passive"))
      (node (ref "U2") (pin "12") (pinfunction "PH_12") (pintype "passive"))
    )
    (net (code "17") (name "/PVIN") (class "Default")
      (node (ref "C11") (pin "1") (pinfunction "1_1") (pintype "passive"))
      (node (ref "C29") (pin "1") (pinfunction "1_1") (pintype "passive"))
      (node (ref "C30") (pin "1") (pinfunction "1_1") (pintype "passive"))
      (node (ref "C67") (pin "1") (pinfunction "1_1") (pintype "passive"))
      (node (ref "C68") (pin "1") (pinfunction "1_1") (pintype "passive"))
      (node (ref "C69") (pin "1") (pinfunction "1_1") (pintype "passive"))
      (node (ref "C7") (pin "1") (pinfunction "1_1") (pintype "passive"))
      (node (ref "FB1") (pin "2") (pinfunction "2_2") (pintype "passive"))
      (node (ref "U19") (pin "12") (pinfunction "VIN2_12") (pintype "passive"))
      (node (ref "U19") (pin "8") (pinfunction "VIN1_8") (pintype "passive"))
      (node (ref "U2") (pin "4") (pinfunction "PVIN_4") (pintype "passive"))
      (node (ref "U2") (pin "5") (pinfunction "PVIN_5") (pintype "passive"))
      (node (ref "U2") (pin "6") (pinfunction "VIN_6") (pintype "passive"))
    )
    (net (code "18") (name "/SCL") (class "Default")
      (node (ref "R23") (pin "2") (pinfunction "2_2") (pintype "passive"))
      (node (ref "U20") (pin "6") (pinfunction "SCL_6") (pintype "passive"))
      (node (ref "U4") (pin "5") (pinfunction "SCLK/SCL_5") (pintype "passive"))
    )
    (net (code "19") (name "/SDA") (class "Default")
      (node (ref "R24") (pin "2") (pinfunction "2_2") (pintype "passive"))
      (node (ref "U20") (pin "5") (pinfunction "SDA_5") (pintype "passive"))
      (node (ref "U4") (pin "7") (pinfunction "SDIN/SDA_7") (pintype "passive"))
    )
    (net (code "20") (name "/VOUT") (class "Default")
      (node (ref "C13") (pin "1") (pinfunction "1_1") (pintype "passive"))
      (node (ref "C14") (pin "1") (pinfunction "1_1") (pintype "passive"))
      (node (ref "C15") (pin "1") (pinfunction "1_1") (pintype "passive"))
      (node (ref "C16") (pin "1") (pinfunction "1_1") (pintype "passive"))
      (node (ref "C17") (pin "1") (pinfunction "1_1") (pintype "passive"))
      (node (ref "C18") (pin "1") (pinfunction "1_1") (pintype "passive"))
      (node (ref "C19") (pin "1") (pinfunction "1_1") (pintype "passive"))
      (node (ref "D5") (pin "1") (pinfunction "K_1") (pintype "passive"))
      (node (ref "FB2") (pin "1") (pinfunction "1_1") (pintype "passive"))
      (node (ref "L2") (pin "2") (pinfunction "2_2") (pintype "passive"))
      (node (ref "R12") (pin "2") (pinfunction "2_2") (pintype "passive"))
      (node (ref "R63") (pin "2") (pinfunction "2_2") (pintype "passive"))
      (node (ref "R83") (pin "2") (pinfunction "2_2") (pintype "passive"))
      (node (ref "R9") (pin "2") (pinfunction "2_2") (pintype "passive"))
      (node (ref "XP2") (pin "1") (pinfunction "1_1") (pintype "passive"))
    )
    (net (code "21") (name "/VOUT_SHUNT") (class "Default")
      (node (ref "FB2") (pin "2") (pinfunction "2_2") (pintype "passive"))
      (node (ref "R1") (pin "2") (pinfunction "2_2") (pintype "passive"))
      (node (ref "R2") (pin "2") (pinfunction "2_2") (pintype "passive"))
      (node (ref "XP1") (pin "2") (pinfunction "2_2") (pintype "passive"))
      (node (ref "XP2") (pin "2") (pinfunction "2_2") (pintype "passive"))
    )
    (net (code "22") (name "/VREFIO") (class "Default")
      (node (ref "C34") (pin "1") (pinfunction "1_1") (pintype "passive"))
      (node (ref "C35") (pin "1") (pinfunction "1_1") (pintype "passive"))
      (node (ref "U4") (pin "8") (pinfunction "VREFIO_8") (pintype "passive"))
    )
    (net (code "23") (name "3V3") (class "Default")
      (node (ref "C20") (pin "1") (pinfunction "1_1") (pintype "passive"))
      (node (ref "C27") (pin "1") (pinfunction "1_1") (pintype "passive"))
      (node (ref "C28") (pin "1") (pinfunction "1_1") (pintype "passive"))
      (node (ref "C3") (pin "1") (pinfunction "1_1") (pintype "passive"))
      (node (ref "C74") (pin "2") (pinfunction "2_2") (pintype "passive"))
      (node (ref "L3") (pin "1") (pinfunction "1_1") (pintype "passive"))
      (node (ref "R59") (pin "2") (pinfunction "2_2") (pintype "passive"))
      (node (ref "R8") (pin "2") (pinfunction "2_2") (pintype "passive"))
      (node (ref "U1") (pin "5") (pinfunction "VCC_5") (pintype "passive"))
      (node (ref "U20") (pin "8") (pinfunction "VCC_8") (pintype "passive"))
      (node (ref "U3") (pin "5") (pinfunction "VCC_5") (pintype "passive"))
    )
    (net (code "24") (name "5V") (class "Default")
      (node (ref "Q1") (pin "2") (pinfunction "S_2") (pintype "passive"))
      (node (ref "R19") (pin "2") (pinfunction "2_2") (pintype "passive"))
      (node (ref "R4") (pin "2") (pinfunction "2_2") (pintype "passive"))
    )
    (net (code "25") (name "15-26VIN_F") (class "Default")
      (node (ref "C5") (pin "1") (pinfunction "1_1") (pintype "passive"))
      (node (ref "C8") (pin "1") (pinfunction "1_1") (pintype "passive"))
      (node (ref "C9") (pin "1") (pinfunction "1_1") (pintype "passive"))
      (node (ref "L1") (pin "1") (pinfunction "1_1") (pintype "passive"))
      (node (ref "R5") (pin "1") (pinfunction "1_1") (pintype "passive"))
    )
    (net (code "26") (name "DGND") (class "Default")
      (node (ref "C10") (pin "2") (pinfunction "2_2") (pintype "passive"))
      (node (ref "C11") (pin "2") (pinfunction "2_2") (pintype "passive"))
      (node (ref "C13") (pin "2") (pinfunction "2_2") (pintype "passive"))
      (node (ref "C14") (pin "2") (pinfunction "2_2") (pintype "passive"))
      (node (ref "C15") (pin "2") (pinfunction "2_2") (pintype "passive"))
      (node (ref "C16") (pin "2") (pinfunction "2_2") (pintype "passive"))
      (node (ref "C17") (pin "2") (pinfunction "2_2") (pintype "passive"))
      (node (ref "C18") (pin "2") (pinfunction "2_2") (pintype "passive"))
      (node (ref "C19") (pin "2") (pinfunction "2_2") (pintype "passive"))
      (node (ref "C20") (pin "2") (pinfunction "2_2") (pintype "passive"))
      (node (ref "C23") (pin "2") (pinfunction "2_2") (pintype "passive"))
      (node (ref "C25") (pin "2") (pinfunction "2_2") (pintype "passive"))
      (node (ref "C26") (pin "2") (pinfunction "2_2") (pintype "passive"))
      (node (ref "C27") (pin "2") (pinfunction "2_2") (pintype "passive"))
      (node (ref "C28") (pin "2") (pinfunction "2_2") (pintype "passive"))
      (node (ref "C29") (pin "2") (pinfunction "2_2") (pintype "passive"))
      (node (ref "C3") (pin "2") (pinfunction "2_2") (pintype "passive"))
      (node (ref "C30") (pin "2") (pinfunction "2_2") (pintype "passive"))
      (node (ref "C31") (pin "2") (pinfunction "2_2") (pintype "passive"))
      (node (ref "C32") (pin "2") (pinfunction "2_2") (pintype "passive"))
      (node (ref "C33") (pin "2") (pinfunction "2_2") (pintype "passive"))
      (node (ref "C34") (pin "2") (pinfunction "2_2") (pintype "passive"))
      (node (ref "C35") (pin "2") (pinfunction "2_2") (pintype "passive"))
      (node (ref "C4") (pin "2") (pinfunction "2_2") (pintype "passive"))
      (node (ref "C5") (pin "2") (pinfunction "2_2") (pintype "passive"))
      (node (ref "C6") (pin "2") (pinfunction "2_2") (pintype "passive"))
      (node (ref "C67") (pin "2") (pinfunction "2_2") (pintype "passive"))
      (node (ref "C68") (pin "2") (pinfunction "2_2") (pintype "passive"))
      (node (ref "C69") (pin "2") (pinfunction "2_2") (pintype "passive"))
      (node (ref "C7") (pin "2") (pinfunction "2_2") (pintype "passive"))
      (node (ref "C72") (pin "2") (pinfunction "2_2") (pintype "passive"))
      (node (ref "C74") (pin "1") (pinfunction "1_1") (pintype "passive"))
      (node (ref "C77") (pin "2") (pinfunction "2_2") (pintype "passive"))
      (node (ref "C8") (pin "2") (pinfunction "2_2") (pintype "passive"))
      (node (ref "C9") (pin "2") (pinfunction "2_2") (pintype "passive"))
      (node (ref "Q2") (pin "2") (pinfunction "E_2") (pintype "passive"))
      (node (ref "R103") (pin "1") (pinfunction "1_1") (pintype "passive"))
      (node (ref "R11") (pin "1") (pinfunction "1_1") (pintype "passive"))
      (node (ref "R13") (pin "2") (pinfunction "2_2") (pintype "passive"))
      (node (ref "R15") (pin "1") (pinfunction "1_1") (pintype "passive"))
      (node (ref "R16") (pin "1") (pinfunction "1_1") (pintype "passive"))
      (node (ref "R22") (pin "1") (pinfunction "1_1") (pintype "passive"))
      (node (ref "R26") (pin "2") (pinfunction "2_2") (pintype "passive"))
      (node (ref "R3") (pin "2") (pinfunction "2_2") (pintype "passive"))
      (node (ref "R58") (pin "2") (pinfunction "2_2") (pintype "passive"))
      (node (ref "R66") (pin "1") (pinfunction "1_1") (pintype "passive"))
      (node (ref "R67") (pin "1") (pinfunction "1_1") (pintype "passive"))
      (node (ref "R74") (pin "2") (pinfunction "2_2") (pintype "passive"))
      (node (ref "R9") (pin "1") (pinfunction "1_1") (pintype "passive"))
      (node (ref "R90") (pin "1") (pinfunction "1_1") (pintype "passive"))
      (node (ref "R91") (pin "1") (pinfunction "1_1") (pintype "passive"))
      (node (ref "R95") (pin "1") (pinfunction "1_1") (pintype "passive"))
      (node (ref "R98") (pin "1") (pinfunction "1_1") (pintype "passive"))
      (node (ref "R99") (pin "1") (pinfunction "1_1") (pintype "passive"))
      (node (ref "U1") (pin "2") (pinfunction "GND_2") (pintype "passive"))
      (node (ref "U19") (pin "11") (pinfunction "PGND2_11") (pintype "passive"))
      (node (ref "U19") (pin "3") (pinfunction "AGND_3") (pintype "passive"))
      (node (ref "U19") (pin "9") (pinfunction "PGND1_9") (pintype "passive"))
      (node (ref "U2") (pin "15") (pinfunction "GND(EP)_15") (pintype "passive"))
      (node (ref "U2") (pin "2") (pinfunction "GND_2") (pintype "passive"))
      (node (ref "U2") (pin "3") (pinfunction "GND_3") (pintype "passive"))
      (node (ref "U20") (pin "3") (pinfunction "A2_3") (pintype "passive"))
      (node (ref "U20") (pin "4") (pinfunction "GND_4") (pintype "passive"))
      (node (ref "U20") (pin "9") (pinfunction "GND(EP)_9") (pintype "passive"))
      (node (ref "U3") (pin "2") (pinfunction "GND_2") (pintype "passive"))
      (node (ref "U4") (pin "3") (pinfunction "AGND_3") (pintype "passive"))
      (node (ref "X1") (pin "1") (pinfunction "1_1") (pintype "passive"))
      (node (ref "XP1") (pin "1") (pinfunction "1_1") (pintype "passive"))
      (node (ref "XP2") (pin "3") (pinfunction "3_3") (pintype "passive"))
      (node (ref "XP2") (pin "4") (pinfunction "4_4") (pintype "passive"))
    )
    (net (code "27") (name "Net-(C2-Pad1)") (class "Default")
      (node (ref "C2") (pin "1") (pinfunction "1_1") (pintype "passive"))
      (node (ref "R2") (pin "1") (pinfunction "1_1") (pintype "passive"))
    )
    (net (code "28") (name "Net-(C4-Pad1)") (class "Default")
      (node (ref "C4") (pin "1") (pinfunction "1_1") (pintype "passive"))
      (node (ref "R6") (pin "2") (pinfunction "2_2") (pintype "passive"))
    )
    (net (code "29") (name "Net-(C10-Pad1)") (class "Default")
      (node (ref "C10") (pin "1") (pinfunction "1_1") (pintype "passive"))
      (node (ref "C6") (pin "1") (pinfunction "1_1") (pintype "passive"))
      (node (ref "FB1") (pin "1") (pinfunction "1_1") (pintype "passive"))
      (node (ref "L1") (pin "2") (pinfunction "2_2") (pintype "passive"))
      (node (ref "R5") (pin "2") (pinfunction "2_2") (pintype "passive"))
    )
    (net (code "30") (name "Net-(C12-Pad1)") (class "Default")
      (node (ref "C12") (pin "1") (pinfunction "1_1") (pintype "passive"))
      (node (ref "R7") (pin "1") (pinfunction "1_1") (pintype "passive"))
    )
    (net (code "31") (name "Net-(C21-Pad1)") (class "Default")
      (node (ref "C21") (pin "1") (pinfunction "1_1") (pintype "passive"))
      (node (ref "R63") (pin "1") (pinfunction "1_1") (pintype "passive"))
    )
    (net (code "32") (name "Net-(C22-Pad2)") (class "Default")
      (node (ref "C22") (pin "2") (pinfunction "2_2") (pintype "passive"))
      (node (ref "R15") (pin "2") (pinfunction "2_2") (pintype "passive"))
    )
    (net (code "33") (name "Net-(C26-Pad1)") (class "Default")
      (node (ref "C26") (pin "1") (pinfunction "1_1") (pintype "passive"))
      (node (ref "R20") (pin "2") (pinfunction "2_2") (pintype "passive"))
      (node (ref "R21") (pin "1") (pinfunction "1_1") (pintype "passive"))
    )
    (net (code "34") (name "Net-(C70-Pad1)") (class "Default")
      (node (ref "C70") (pin "1") (pinfunction "1_1") (pintype "passive"))
      (node (ref "R102") (pin "2") (pinfunction "2_2") (pintype "passive"))
      (node (ref "R103") (pin "2") (pinfunction "2_2") (pintype "passive"))
    )
    (net (code "35") (name "Net-(D1-A)") (class "Default")
      (node (ref "D1") (pin "2") (pinfunction "A_2") (pintype "passive"))
      (node (ref "R19") (pin "1") (pinfunction "1_1") (pintype "passive"))
    )
    (net (code "36") (name "Net-(D5-A)") (class "Default")
      (node (ref "D5") (pin "2") (pinfunction "A_2") (pintype "passive"))
      (node (ref "R14") (pin "2") (pinfunction "2_2") (pintype "passive"))
    )
    (net (code "37") (name "Net-(Q1-D)") (class "Default")
      (node (ref "Q1") (pin "3") (pinfunction "D_3") (pintype "passive"))
      (node (ref "R62") (pin "1") (pinfunction "1_1") (pintype "passive"))
    )
    (net (code "38") (name "Net-(Q2-B)") (class "Default")
      (node (ref "Q2") (pin "1") (pinfunction "B_1") (pintype "passive"))
      (node (ref "R14") (pin "1") (pinfunction "1_1") (pintype "passive"))
      (node (ref "R16") (pin "2") (pinfunction "2_2") (pintype "passive"))
    )
    (net (code "39") (name "Net-(U1-B1)") (class "Default")
      (node (ref "C21") (pin "2") (pinfunction "2_2") (pintype "passive"))
      (node (ref "R12") (pin "1") (pinfunction "1_1") (pintype "passive"))
      (node (ref "R22") (pin "2") (pinfunction "2_2") (pintype "passive"))
      (node (ref "U1") (pin "3") (pinfunction "B1_3") (pintype "passive"))
    )
    (net (code "40") (name "Net-(U1-B2)") (class "Default")
      (node (ref "C2") (pin "2") (pinfunction "2_2") (pintype "passive"))
      (node (ref "R1") (pin "1") (pinfunction "1_1") (pintype "passive"))
      (node (ref "R67") (pin "2") (pinfunction "2_2") (pintype "passive"))
      (node (ref "U1") (pin "1") (pinfunction "B2_1") (pintype "passive"))
    )
    (net (code "41") (name "Net-(U2-COMP)") (class "Default")
      (node (ref "C22") (pin "1") (pinfunction "1_1") (pintype "passive"))
      (node (ref "C23") (pin "1") (pinfunction "1_1") (pintype "passive"))
      (node (ref "U2") (pin "8") (pinfunction "COMP_8") (pintype "passive"))
    )
    (net (code "42") (name "Net-(U2-RT{slash}CLK)") (class "Default")
      (node (ref "R10") (pin "2") (pinfunction "2_2") (pintype "passive"))
      (node (ref "R11") (pin "2") (pinfunction "2_2") (pintype "passive"))
      (node (ref "R99") (pin "2") (pinfunction "2_2") (pintype "passive"))
      (node (ref "U2") (pin "1") (pinfunction "RT/CLK_1") (pintype "passive"))
    )
    (net (code "43") (name "Net-(U2-SS{slash}TR)") (class "Default")
      (node (ref "C25") (pin "1") (pinfunction "1_1") (pintype "passive"))
      (node (ref "U2") (pin "9") (pinfunction "SS/TR_9") (pintype "passive"))
    )
    (net (code "44") (name "Net-(U4-nSYNC{slash}A0)") (class "Default")
      (node (ref "R23") (pin "1") (pinfunction "1_1") (pintype "passive"))
      (node (ref "R24") (pin "1") (pinfunction "1_1") (pintype "passive"))
      (node (ref "R25") (pin "1") (pinfunction "1_1") (pintype "passive"))
      (node (ref "R26") (pin "1") (pinfunction "1_1") (pintype "passive"))
      (node (ref "U4") (pin "6") (pinfunction "nSYNC/A0_6") (pintype "passive"))
    )
    (net (code "45") (name "Net-(U19-BIAS)") (class "Default")
      (node (ref "C77") (pin "1") (pinfunction "1_1") (pintype "passive"))
      (node (ref "R83") (pin "1") (pinfunction "1_1") (pintype "passive"))
      (node (ref "U19") (pin "1") (pinfunction "BIAS_1") (pintype "passive"))
    )
    (net (code "46") (name "Net-(U19-CBOOT)") (class "Default")
      (node (ref "C71") (pin "2") (pinfunction "2_2") (pintype "passive"))
      (node (ref "R65") (pin "2") (pinfunction "2_2") (pintype "passive"))
      (node (ref "U19") (pin "14") (pinfunction "CBOOT_14") (pintype "passive"))
    )
    (net (code "47") (name "Net-(U19-RBOOT)") (class "Default")
      (node (ref "R65") (pin "1") (pinfunction "1_1") (pintype "passive"))
      (node (ref "U19") (pin "13") (pinfunction "RBOOT_13") (pintype "passive"))
    )
    (net (code "48") (name "Net-(U19-RT)") (class "Default")
      (node (ref "R66") (pin "2") (pinfunction "2_2") (pintype "passive"))
      (node (ref "U19") (pin "6") (pinfunction "RT_6") (pintype "passive"))
    )
    (net (code "49") (name "Net-(U19-VCC)") (class "Default")
      (node (ref "C72") (pin "1") (pinfunction "1_1") (pintype "passive"))
      (node (ref "U19") (pin "2") (pinfunction "VCC_2") (pintype "passive"))
    )
    (net (code "50") (name "Net-(U20-A0)") (class "Default")
      (node (ref "R58") (pin "1") (pinfunction "1_1") (pintype "passive"))
      (node (ref "R8") (pin "1") (pinfunction "1_1") (pintype "passive"))
      (node (ref "U20") (pin "1") (pinfunction "A0_1") (pintype "passive"))
    )
    (net (code "51") (name "Net-(U20-A1)") (class "Default")
      (node (ref "R59") (pin "1") (pinfunction "1_1") (pintype "passive"))
      (node (ref "R74") (pin "1") (pinfunction "1_1") (pintype "passive"))
      (node (ref "U20") (pin "2") (pinfunction "A1_2") (pintype "passive"))
    )
    (net (code "52") (name "unconnected-(MH1-Pad0)") (class "Default")
      (node (ref "MH1") (pin "0") (pinfunction "0_0") (pintype "passive"))
    )
    (net (code "53") (name "unconnected-(MH4-Pad0)") (class "Default")
      (node (ref "MH4") (pin "0") (pinfunction "0_0") (pintype "passive"))
    )
    (net (code "54") (name "unconnected-(U2-PWRGD-Pad14)") (class "Default")
      (node (ref "U2") (pin "14") (pinfunction "PWRGD_14") (pintype "passive+no_connect"))
    )
    (net (code "55") (name "unconnected-(U19-PGOOD-Pad5)") (class "Default")
      (node (ref "U19") (pin "5") (pinfunction "PGOOD_5") (pintype "passive+no_connect"))
    )
    (net (code "56") (name "unconnected-(U20-~{EVENT}-Pad7)") (class "Default")
      (node (ref "U20") (pin "7") (pinfunction "~{EVENT}_7") (pintype "passive+no_connect"))
    )
  )
)
